# deepshark_power_switch.net
KiCad netlist of a schematic drawn in Altium Designer
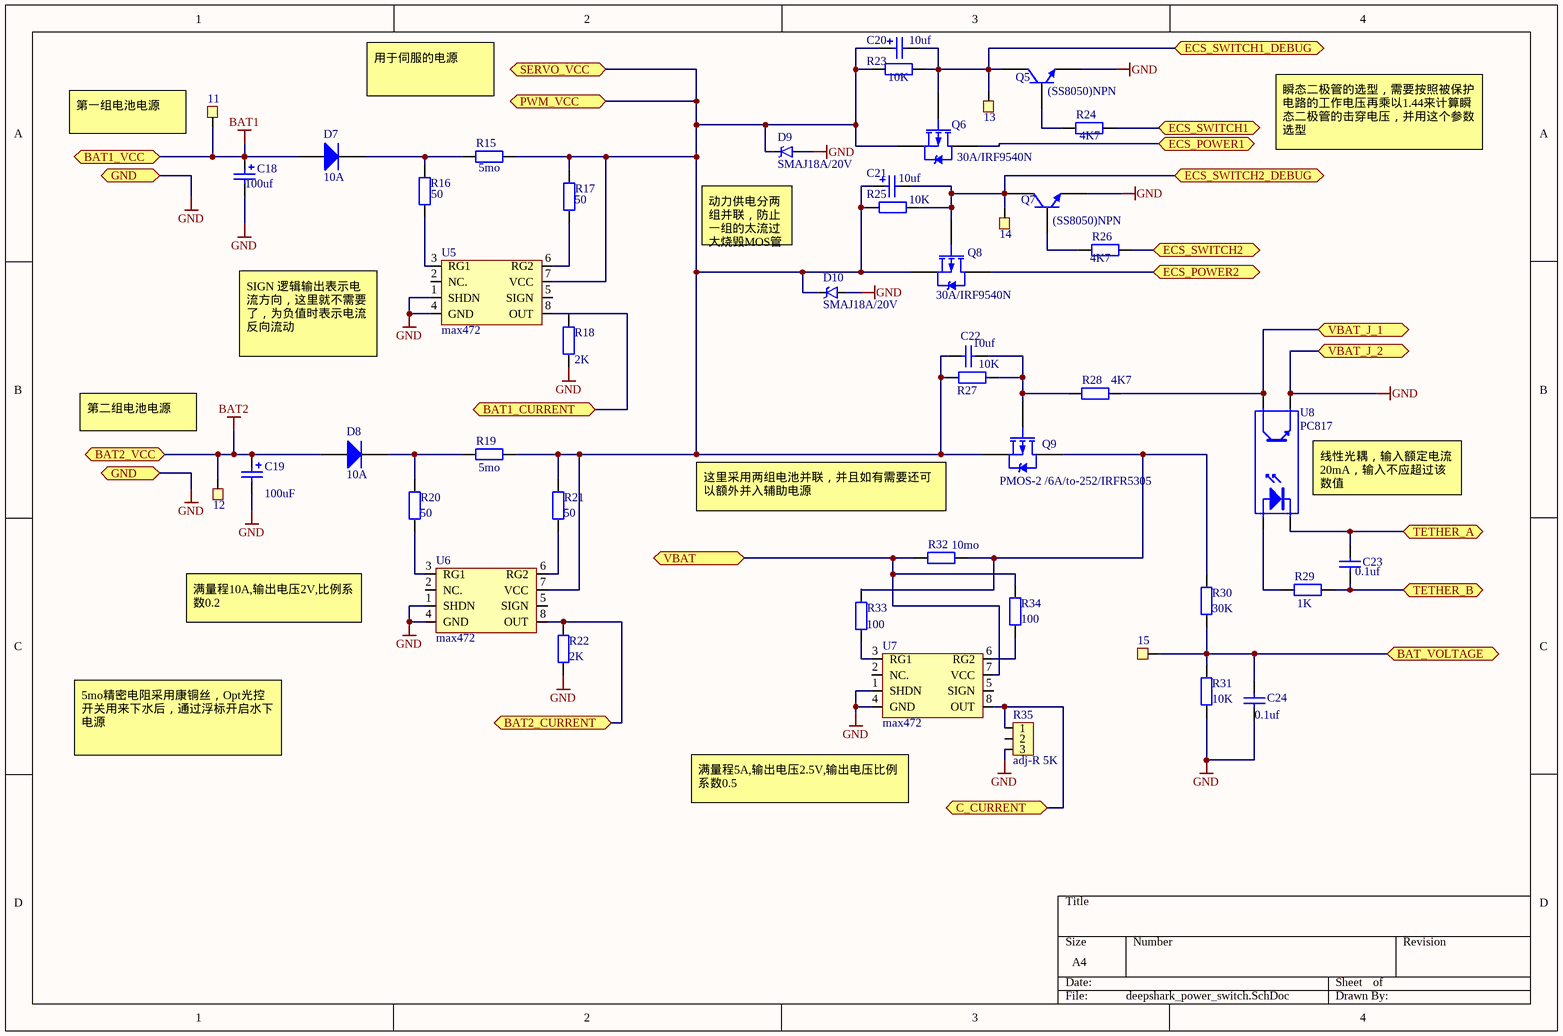
[diagram p0: deepshark_power_switch.SchDoc]

(export (version "E")
  (design (tool "Eeschema 10.0.6"))
  (components
    (comp (ref "11") (value "TP") (footprint "TestPoint") (libsource (lib "") (part "TP_2")))
    (comp (ref "12") (value "TP") (footprint "TestPoint") (libsource (lib "deepshark_sch_lib") (part "TP")))
    (comp (ref "13") (value "TP") (footprint "TestPoint") (libsource (lib "deepshark_sch_lib") (part "TP")))
    (comp (ref "14") (value "TP") (footprint "TestPoint") (libsource (lib "deepshark_sch_lib") (part "TP")))
    (comp (ref "15") (value "TP") (footprint "TestPoint") (libsource (lib "") (part "TP_1")))
    (comp (ref "C18")
      (value "100uf")
      (footprint "100uf-25v")
      (description "Polarized Capacitor (Axial)")
      (fields (field (name "Comment") "Cap Pol2") (field (name "PUBLISHER") "Altium Limited"))
      (libsource (lib "Miscellaneous Devices") (part "Cap Pol2"))
    )
    (comp (ref "C19")
      (value "100uF")
      (footprint "100uf-25v")
      (description "Polarized Capacitor (Axial)")
      (fields (field (name "Comment") "Cap Pol2") (field (name "PUBLISHER") "Altium Limited"))
      (libsource (lib "Miscellaneous Devices") (part "Cap Pol2"))
    )
    (comp (ref "C20")
      (value "10uf")
      (footprint "1206")
      (description "Polarized Capacitor (Axial)")
      (fields (field (name "Comment") "Cap Pol2") (field (name "PUBLISHER") "Altium Limited"))
      (libsource (lib "Miscellaneous Devices") (part "Cap Pol2"))
    )
    (comp (ref "C21")
      (value "10uf")
      (footprint "1206")
      (description "Polarized Capacitor (Axial)")
      (fields (field (name "Comment") "Cap Pol2") (field (name "PUBLISHER") "Altium Limited"))
      (libsource (lib "Miscellaneous Devices") (part "Cap Pol2"))
    )
    (comp (ref "C22")
      (value "10uf")
      (footprint "1206")
      (description "Capacitor")
      (fields (field (name "Comment") "Cap") (field (name "PUBLISHER") "Altium Limited"))
      (libsource (lib "Miscellaneous Devices") (part "Cap"))
    )
    (comp (ref "C23")
      (value "0.1uf")
      (footprint "6-0805_M")
      (description "Capacitor")
      (fields (field (name "Comment") "Cap") (field (name "PUBLISHER") "Altium Limited"))
      (libsource (lib "Miscellaneous Devices") (part "Cap"))
    )
    (comp (ref "C24")
      (value "0.1uf")
      (footprint "6-0805_M")
      (description "Capacitor")
      (fields (field (name "Comment") "Cap") (field (name "PUBLISHER") "Altium Limited"))
      (libsource (lib "Miscellaneous Devices") (part "Cap"))
    )
    (comp (ref "D7")
      (value "10A")
      (footprint "10A-Rectifier")
      (description "Default Diode")
      (fields (field (name "PUBLISHER") "Altium Limited"))
      (libsource (lib "Miscellaneous Devices") (part "Diode"))
    )
    (comp (ref "D8")
      (value "10A")
      (footprint "10A-Rectifier")
      (description "Default Diode")
      (fields (field (name "PUBLISHER") "Altium Limited"))
      (libsource (lib "Miscellaneous Devices") (part "Diode"))
    )
    (comp (ref "D9") (value "SMAJ18A/20V") (footprint "SMBJ6.5A") (libsource (lib "常用2") (part "DW")))
    (comp (ref "D10") (value "SMAJ18A/20V") (footprint "SMBJ6.5A") (libsource (lib "常用2") (part "DW")))
    (comp (ref "Q5")
      (value "(SS8050)NPN")
      (footprint "SOT89M")
      (description "NPN Bipolar Transistor")
      (fields (field (name "PUBLISHER") "Altium Limited"))
      (libsource (lib "Miscellaneous Devices") (part "NPN"))
    )
    (comp (ref "Q6")
      (value "30A/IRF9540N")
      (footprint "my-TO-220AB")
      (description "P-Channel Power MOSFET")
      (fields (field (name "PUBLISHER") "Altium Limited"))
      (libsource (lib "Miscellaneous Devices") (part "PMOS-2"))
    )
    (comp (ref "Q7")
      (value "(SS8050)NPN")
      (footprint "SOT89M")
      (description "NPN Bipolar Transistor")
      (fields (field (name "PUBLISHER") "Altium Limited"))
      (libsource (lib "Miscellaneous Devices") (part "NPN"))
    )
    (comp (ref "Q8")
      (value "30A/IRF9540N")
      (footprint "my-TO-220AB")
      (description "P-Channel Power MOSFET")
      (fields (field (name "PUBLISHER") "Altium Limited"))
      (libsource (lib "Miscellaneous Devices") (part "PMOS-2"))
    )
    (comp (ref "Q9")
      (value "PMOS-2 /6A/to-252/IRFR5305")
      (footprint "TO-252AA")
      (description "P-Channel Power MOSFET")
      (fields (field (name "PUBLISHER") "Altium Limited"))
      (libsource (lib "") (part "PMOS-2_1"))
    )
    (comp (ref "R15")
      (value "5mo")
      (footprint "5mo")
      (description "Resistor")
      (fields (field (name "Comment") "Res2") (field (name "PUBLISHER") "Altium Limited"))
      (libsource (lib "Miscellaneous Devices") (part "Res2"))
    )
    (comp (ref "R16")
      (value "50")
      (footprint "my0603")
      (description "Resistor")
      (fields (field (name "Comment") "Res2") (field (name "PUBLISHER") "Altium Limited"))
      (libsource (lib "") (part "Res2_1"))
    )
    (comp (ref "R17")
      (value "50")
      (footprint "my0603")
      (description "Resistor")
      (fields (field (name "Comment") "Res2") (field (name "PUBLISHER") "Altium Limited"))
      (libsource (lib "") (part "Res2_1"))
    )
    (comp (ref "R18")
      (value "2K")
      (footprint "6-0805_M")
      (description "Resistor")
      (fields (field (name "Comment") "Res2") (field (name "PUBLISHER") "Altium Limited"))
      (libsource (lib "") (part "Res2_1"))
    )
    (comp (ref "R19")
      (value "5mo")
      (footprint "5mo")
      (description "Resistor")
      (fields (field (name "Comment") "Res2") (field (name "PUBLISHER") "Altium Limited"))
      (libsource (lib "Miscellaneous Devices") (part "Res2"))
    )
    (comp (ref "R20")
      (value "50")
      (footprint "my0603")
      (description "Resistor")
      (fields (field (name "Comment") "Res2") (field (name "PUBLISHER") "Altium Limited"))
      (libsource (lib "") (part "Res2_1"))
    )
    (comp (ref "R21")
      (value "50")
      (footprint "my0603")
      (description "Resistor")
      (fields (field (name "Comment") "Res2") (field (name "PUBLISHER") "Altium Limited"))
      (libsource (lib "") (part "Res2_1"))
    )
    (comp (ref "R22")
      (value "2K")
      (footprint "6-0805_M")
      (description "Resistor")
      (fields (field (name "Comment") "Res2") (field (name "PUBLISHER") "Altium Limited"))
      (libsource (lib "") (part "Res2_1"))
    )
    (comp (ref "R23")
      (value "10K")
      (footprint "6-0805_M")
      (description "Resistor")
      (fields (field (name "Comment") "Res2") (field (name "PUBLISHER") "Altium Limited"))
      (libsource (lib "Miscellaneous Devices") (part "Res2"))
    )
    (comp (ref "R24")
      (value "4K7")
      (footprint "6-0805_M")
      (description "Resistor")
      (fields (field (name "Comment") "Res2") (field (name "PUBLISHER") "Altium Limited"))
      (libsource (lib "") (part "Res2_2"))
    )
    (comp (ref "R25")
      (value "10K")
      (footprint "6-0805_M")
      (description "Resistor")
      (fields (field (name "Comment") "Res2") (field (name "PUBLISHER") "Altium Limited"))
      (libsource (lib "Miscellaneous Devices") (part "Res2"))
    )
    (comp (ref "R26")
      (value "4K7")
      (footprint "6-0805_M")
      (description "Resistor")
      (fields (field (name "Comment") "Res2") (field (name "PUBLISHER") "Altium Limited"))
      (libsource (lib "Miscellaneous Devices") (part "Res2"))
    )
    (comp (ref "R27")
      (value "10K")
      (footprint "6-0805_M")
      (description "Resistor")
      (fields (field (name "Comment") "Res2") (field (name "PUBLISHER") "Altium Limited"))
      (libsource (lib "Miscellaneous Devices") (part "Res2"))
    )
    (comp (ref "R28")
      (value "4K7")
      (footprint "6-0805_M")
      (description "Resistor")
      (fields (field (name "Comment") "Res2") (field (name "PUBLISHER") "Altium Limited"))
      (libsource (lib "Miscellaneous Devices") (part "Res2"))
    )
    (comp (ref "R29")
      (value "1K")
      (footprint "6-0805_M")
      (description "Resistor")
      (fields (field (name "Comment") "Res2") (field (name "PUBLISHER") "Altium Limited"))
      (libsource (lib "Miscellaneous Devices") (part "Res2"))
    )
    (comp (ref "R30")
      (value "30K")
      (footprint "6-0805_M")
      (description "Resistor")
      (fields (field (name "Comment") "Res2") (field (name "PUBLISHER") "Altium Limited"))
      (libsource (lib "") (part "Res2_1"))
    )
    (comp (ref "R31")
      (value "10K")
      (footprint "6-0805_M")
      (description "Resistor")
      (fields (field (name "Comment") "Res2") (field (name "PUBLISHER") "Altium Limited"))
      (libsource (lib "") (part "Res2_1"))
    )
    (comp (ref "R32")
      (value "10mo")
      (footprint "10mo")
      (description "Resistor")
      (fields (field (name "Comment") "Res2") (field (name "PUBLISHER") "Altium Limited"))
      (libsource (lib "Miscellaneous Devices") (part "Res2"))
    )
    (comp (ref "R33")
      (value "100")
      (footprint "my0603")
      (description "Resistor")
      (fields (field (name "Comment") "Res2") (field (name "PUBLISHER") "Altium Limited"))
      (libsource (lib "") (part "Res2_1"))
    )
    (comp (ref "R34")
      (value "100")
      (footprint "my0603")
      (description "Resistor")
      (fields (field (name "Comment") "Res2") (field (name "PUBLISHER") "Altium Limited"))
      (libsource (lib "") (part "Res2_1"))
    )
    (comp (ref "R35")
      (value "adj-R 5K")
      (footprint "adj-R")
      (libsource (lib "deepshark_sch_lib") (part "adj-R"))
    )
    (comp (ref "U5")
      (value "max472")
      (footprint "SO-8_M")
      (libsource (lib "deepshark_sch_lib") (part "max472"))
    )
    (comp (ref "U6")
      (value "max472")
      (footprint "SO-8_M")
      (libsource (lib "deepshark_sch_lib") (part "max472"))
    )
    (comp (ref "U7")
      (value "max472")
      (footprint "SO-8_M")
      (libsource (lib "deepshark_sch_lib") (part "max472"))
    )
    (comp (ref "U8")
      (value "PC817")
      (footprint "DIP-4")
      (description "4-Pin Phototransistor Optocoupler")
      (fields (field (name "PUBLISHER") "Altium Limited"))
      (libsource (lib "Miscellaneous Devices") (part "Optoisolator1"))
    )
  )
  (nets
    (net (code "1") (name "/BAT1_CURRENT") (class "Default")
      (node (ref "R18") (pin "2") (pinfunction "2_2") (pintype "passive"))
      (node (ref "U5") (pin "8") (pinfunction "OUT_8") (pintype "passive"))
    )
    (net (code "2") (name "/BAT2_CURRENT") (class "Default")
      (node (ref "R22") (pin "2") (pinfunction "2_2") (pintype "passive"))
      (node (ref "U6") (pin "8") (pinfunction "OUT_8") (pintype "passive"))
    )
    (net (code "3") (name "/BAT_VOLTAGE") (class "Default")
      (node (ref "15") (pin "1") (pinfunction "1_1") (pintype "passive"))
      (node (ref "C24") (pin "2") (pinfunction "2_2") (pintype "passive"))
      (node (ref "R30") (pin "1") (pinfunction "1_1") (pintype "passive"))
      (node (ref "R31") (pin "2") (pinfunction "2_2") (pintype "passive"))
    )
    (net (code "4") (name "/C_CURRENT") (class "Default")
      (node (ref "R35") (pin "1") (pinfunction "1_1") (pintype "passive"))
      (node (ref "U7") (pin "8") (pinfunction "OUT_8") (pintype "passive"))
    )
    (net (code "5") (name "/ECS_POWER1") (class "Default")
      (node (ref "Q6") (pin "2") (pinfunction "D_2") (pintype "passive"))
    )
    (net (code "6") (name "/ECS_POWER2") (class "Default")
      (node (ref "Q8") (pin "2") (pinfunction "D_2") (pintype "passive"))
    )
    (net (code "7") (name "/ECS_SWITCH1") (class "Default")
      (node (ref "R24") (pin "1") (pinfunction "1_1") (pintype "passive"))
    )
    (net (code "8") (name "/ECS_SWITCH1_DEBUG") (class "Default")
      (node (ref "13") (pin "1") (pinfunction "1_1") (pintype "passive"))
      (node (ref "C20") (pin "2") (pinfunction "2_2") (pintype "passive"))
      (node (ref "Q5") (pin "1") (pinfunction "C_1") (pintype "passive"))
      (node (ref "Q6") (pin "1") (pinfunction "G_1") (pintype "passive"))
      (node (ref "R23") (pin "2") (pinfunction "2_2") (pintype "passive"))
    )
    (net (code "9") (name "/ECS_SWITCH2") (class "Default")
      (node (ref "R26") (pin "2") (pinfunction "2_2") (pintype "passive"))
    )
    (net (code "10") (name "/ECS_SWITCH2_DEBUG") (class "Default")
      (node (ref "14") (pin "1") (pinfunction "1_1") (pintype "passive"))
      (node (ref "C21") (pin "2") (pinfunction "2_2") (pintype "passive"))
      (node (ref "Q7") (pin "1") (pinfunction "C_1") (pintype "passive"))
      (node (ref "Q8") (pin "1") (pinfunction "G_1") (pintype "passive"))
      (node (ref "R25") (pin "2") (pinfunction "2_2") (pintype "passive"))
    )
    (net (code "11") (name "/PWM_VCC") (class "Default")
      (node (ref "C20") (pin "1") (pinfunction "1_1") (pintype "passive"))
      (node (ref "C21") (pin "1") (pinfunction "1_1") (pintype "passive"))
      (node (ref "C22") (pin "1") (pinfunction "1_1") (pintype "passive"))
      (node (ref "D10") (pin "K") (pintype "passive"))
      (node (ref "D9") (pin "K") (pintype "passive"))
      (node (ref "Q6") (pin "3") (pinfunction "S_3") (pintype "passive"))
      (node (ref "Q8") (pin "3") (pinfunction "S_3") (pintype "passive"))
      (node (ref "Q9") (pin "3") (pinfunction "S_3") (pintype "passive"))
      (node (ref "R15") (pin "2") (pinfunction "2_2") (pintype "passive"))
      (node (ref "R17") (pin "2") (pinfunction "2_2") (pintype "passive"))
      (node (ref "R19") (pin "2") (pinfunction "2_2") (pintype "passive"))
      (node (ref "R21") (pin "2") (pinfunction "2_2") (pintype "passive"))
      (node (ref "R23") (pin "1") (pinfunction "1_1") (pintype "passive"))
      (node (ref "R25") (pin "1") (pinfunction "1_1") (pintype "passive"))
      (node (ref "R27") (pin "1") (pinfunction "1_1") (pintype "passive"))
      (node (ref "U5") (pin "7") (pinfunction "VCC_7") (pintype "passive"))
      (node (ref "U6") (pin "7") (pinfunction "VCC_7") (pintype "passive"))
    )
    (net (code "12") (name "/TETHER_A") (class "Default")
      (node (ref "C23") (pin "2") (pinfunction "2_2") (pintype "passive"))
      (node (ref "U8") (pin "2") (pinfunction "K_2") (pintype "passive"))
    )
    (net (code "13") (name "/TETHER_B") (class "Default")
      (node (ref "C23") (pin "1") (pinfunction "1_1") (pintype "passive"))
      (node (ref "R29") (pin "2") (pinfunction "2_2") (pintype "passive"))
    )
    (net (code "14") (name "/VBAT") (class "Default")
      (node (ref "R32") (pin "1") (pinfunction "1_1") (pintype "passive"))
      (node (ref "R34") (pin "2") (pinfunction "2_2") (pintype "passive"))
      (node (ref "U7") (pin "7") (pinfunction "VCC_7") (pintype "passive"))
    )
    (net (code "15") (name "/VBAT_J_1") (class "Default")
      (node (ref "R28") (pin "2") (pinfunction "2_2") (pintype "passive"))
      (node (ref "U8") (pin "4") (pinfunction "C_4") (pintype "passive"))
    )
    (net (code "16") (name "BAT1") (class "Default")
      (node (ref "11") (pin "1") (pinfunction "1_1") (pintype "passive"))
      (node (ref "C18") (pin "1") (pinfunction "1_1") (pintype "passive"))
      (node (ref "D7") (pin "1") (pinfunction "A_1") (pintype "passive"))
    )
    (net (code "17") (name "BAT2") (class "Default")
      (node (ref "12") (pin "1") (pinfunction "1_1") (pintype "passive"))
      (node (ref "C19") (pin "1") (pinfunction "1_1") (pintype "passive"))
      (node (ref "D8") (pin "1") (pinfunction "A_1") (pintype "passive"))
    )
    (net (code "18") (name "GND") (class "Default")
      (node (ref "C18") (pin "2") (pinfunction "2_2") (pintype "passive"))
      (node (ref "C19") (pin "2") (pinfunction "2_2") (pintype "passive"))
      (node (ref "C24") (pin "1") (pinfunction "1_1") (pintype "passive"))
      (node (ref "D10") (pin "A") (pintype "passive"))
      (node (ref "D9") (pin "A") (pintype "passive"))
      (node (ref "Q5") (pin "3") (pinfunction "E_3") (pintype "passive"))
      (node (ref "Q7") (pin "3") (pinfunction "E_3") (pintype "passive"))
      (node (ref "R18") (pin "1") (pinfunction "1_1") (pintype "passive"))
      (node (ref "R22") (pin "1") (pinfunction "1_1") (pintype "passive"))
      (node (ref "R31") (pin "1") (pinfunction "1_1") (pintype "passive"))
      (node (ref "R35") (pin "3") (pinfunction "3_3") (pintype "passive"))
      (node (ref "U5") (pin "1") (pinfunction "SHDN_1") (pintype "passive"))
      (node (ref "U5") (pin "4") (pinfunction "GND_4") (pintype "passive"))
      (node (ref "U6") (pin "1") (pinfunction "SHDN_1") (pintype "passive"))
      (node (ref "U6") (pin "4") (pinfunction "GND_4") (pintype "passive"))
      (node (ref "U7") (pin "1") (pinfunction "SHDN_1") (pintype "passive"))
      (node (ref "U7") (pin "4") (pinfunction "GND_4") (pintype "passive"))
      (node (ref "U8") (pin "3") (pinfunction "E_3") (pintype "passive"))
    )
    (net (code "19") (name "Net-(D7-K)") (class "Default")
      (node (ref "D7") (pin "2") (pinfunction "K_2") (pintype "passive"))
      (node (ref "R15") (pin "1") (pinfunction "1_1") (pintype "passive"))
      (node (ref "R16") (pin "2") (pinfunction "2_2") (pintype "passive"))
    )
    (net (code "20") (name "Net-(D8-K)") (class "Default")
      (node (ref "D8") (pin "2") (pinfunction "K_2") (pintype "passive"))
      (node (ref "R19") (pin "1") (pinfunction "1_1") (pintype "passive"))
      (node (ref "R20") (pin "2") (pinfunction "2_2") (pintype "passive"))
    )
    (net (code "21") (name "Net-(Q5-B)") (class "Default")
      (node (ref "Q5") (pin "2") (pinfunction "B_2") (pintype "passive"))
      (node (ref "R24") (pin "2") (pinfunction "2_2") (pintype "passive"))
    )
    (net (code "22") (name "Net-(Q7-B)") (class "Default")
      (node (ref "Q7") (pin "2") (pinfunction "B_2") (pintype "passive"))
      (node (ref "R26") (pin "1") (pinfunction "1_1") (pintype "passive"))
    )
    (net (code "23") (name "Net-(Q9-D)") (class "Default")
      (node (ref "Q9") (pin "4") (pinfunction "D_4") (pintype "passive"))
      (node (ref "R30") (pin "2") (pinfunction "2_2") (pintype "passive"))
      (node (ref "R32") (pin "2") (pinfunction "2_2") (pintype "passive"))
      (node (ref "R33") (pin "2") (pinfunction "2_2") (pintype "passive"))
    )
    (net (code "24") (name "Net-(Q9-G)") (class "Default")
      (node (ref "C22") (pin "2") (pinfunction "2_2") (pintype "passive"))
      (node (ref "Q9") (pin "1") (pinfunction "G_1") (pintype "passive"))
      (node (ref "R27") (pin "2") (pinfunction "2_2") (pintype "passive"))
      (node (ref "R28") (pin "1") (pinfunction "1_1") (pintype "passive"))
    )
    (net (code "25") (name "Net-(U5-RG1)") (class "Default")
      (node (ref "R16") (pin "1") (pinfunction "1_1") (pintype "passive"))
      (node (ref "U5") (pin "3") (pinfunction "RG1_3") (pintype "passive"))
    )
    (net (code "26") (name "Net-(U5-RG2)") (class "Default")
      (node (ref "R17") (pin "1") (pinfunction "1_1") (pintype "passive"))
      (node (ref "U5") (pin "6") (pinfunction "RG2_6") (pintype "passive"))
    )
    (net (code "27") (name "Net-(U6-RG1)") (class "Default")
      (node (ref "R20") (pin "1") (pinfunction "1_1") (pintype "passive"))
      (node (ref "U6") (pin "3") (pinfunction "RG1_3") (pintype "passive"))
    )
    (net (code "28") (name "Net-(U6-RG2)") (class "Default")
      (node (ref "R21") (pin "1") (pinfunction "1_1") (pintype "passive"))
      (node (ref "U6") (pin "6") (pinfunction "RG2_6") (pintype "passive"))
    )
    (net (code "29") (name "Net-(U7-RG1)") (class "Default")
      (node (ref "R33") (pin "1") (pinfunction "1_1") (pintype "passive"))
      (node (ref "U7") (pin "3") (pinfunction "RG1_3") (pintype "passive"))
    )
    (net (code "30") (name "Net-(U7-RG2)") (class "Default")
      (node (ref "R34") (pin "1") (pinfunction "1_1") (pintype "passive"))
      (node (ref "U7") (pin "6") (pinfunction "RG2_6") (pintype "passive"))
    )
    (net (code "31") (name "Net-(U8-A)") (class "Default")
      (node (ref "R29") (pin "1") (pinfunction "1_1") (pintype "passive"))
      (node (ref "U8") (pin "1") (pinfunction "A_1") (pintype "passive"))
    )
    (net (code "32") (name "unconnected-(R35-Pad2)") (class "Default")
      (node (ref "R35") (pin "2") (pinfunction "2_2") (pintype "passive"))
    )
    (net (code "33") (name "unconnected-(U5-NC.-Pad2)") (class "Default")
      (node (ref "U5") (pin "2") (pinfunction "NC._2") (pintype "passive"))
    )
    (net (code "34") (name "unconnected-(U5-SIGN-Pad5)") (class "Default")
      (node (ref "U5") (pin "5") (pinfunction "SIGN_5") (pintype "passive"))
    )
    (net (code "35") (name "unconnected-(U6-NC.-Pad2)") (class "Default")
      (node (ref "U6") (pin "2") (pinfunction "NC._2") (pintype "passive"))
    )
    (net (code "36") (name "unconnected-(U6-SIGN-Pad5)") (class "Default")
      (node (ref "U6") (pin "5") (pinfunction "SIGN_5") (pintype "passive"))
    )
    (net (code "37") (name "unconnected-(U7-NC.-Pad2)") (class "Default")
      (node (ref "U7") (pin "2") (pinfunction "NC._2") (pintype "passive"))
    )
    (net (code "38") (name "unconnected-(U7-SIGN-Pad5)") (class "Default")
      (node (ref "U7") (pin "5") (pinfunction "SIGN_5") (pintype "passive"))
    )
  )
)
